# Intermediate_LCL_Top_20230320.net
KiCad netlist of a schematic drawn in Altium Designer
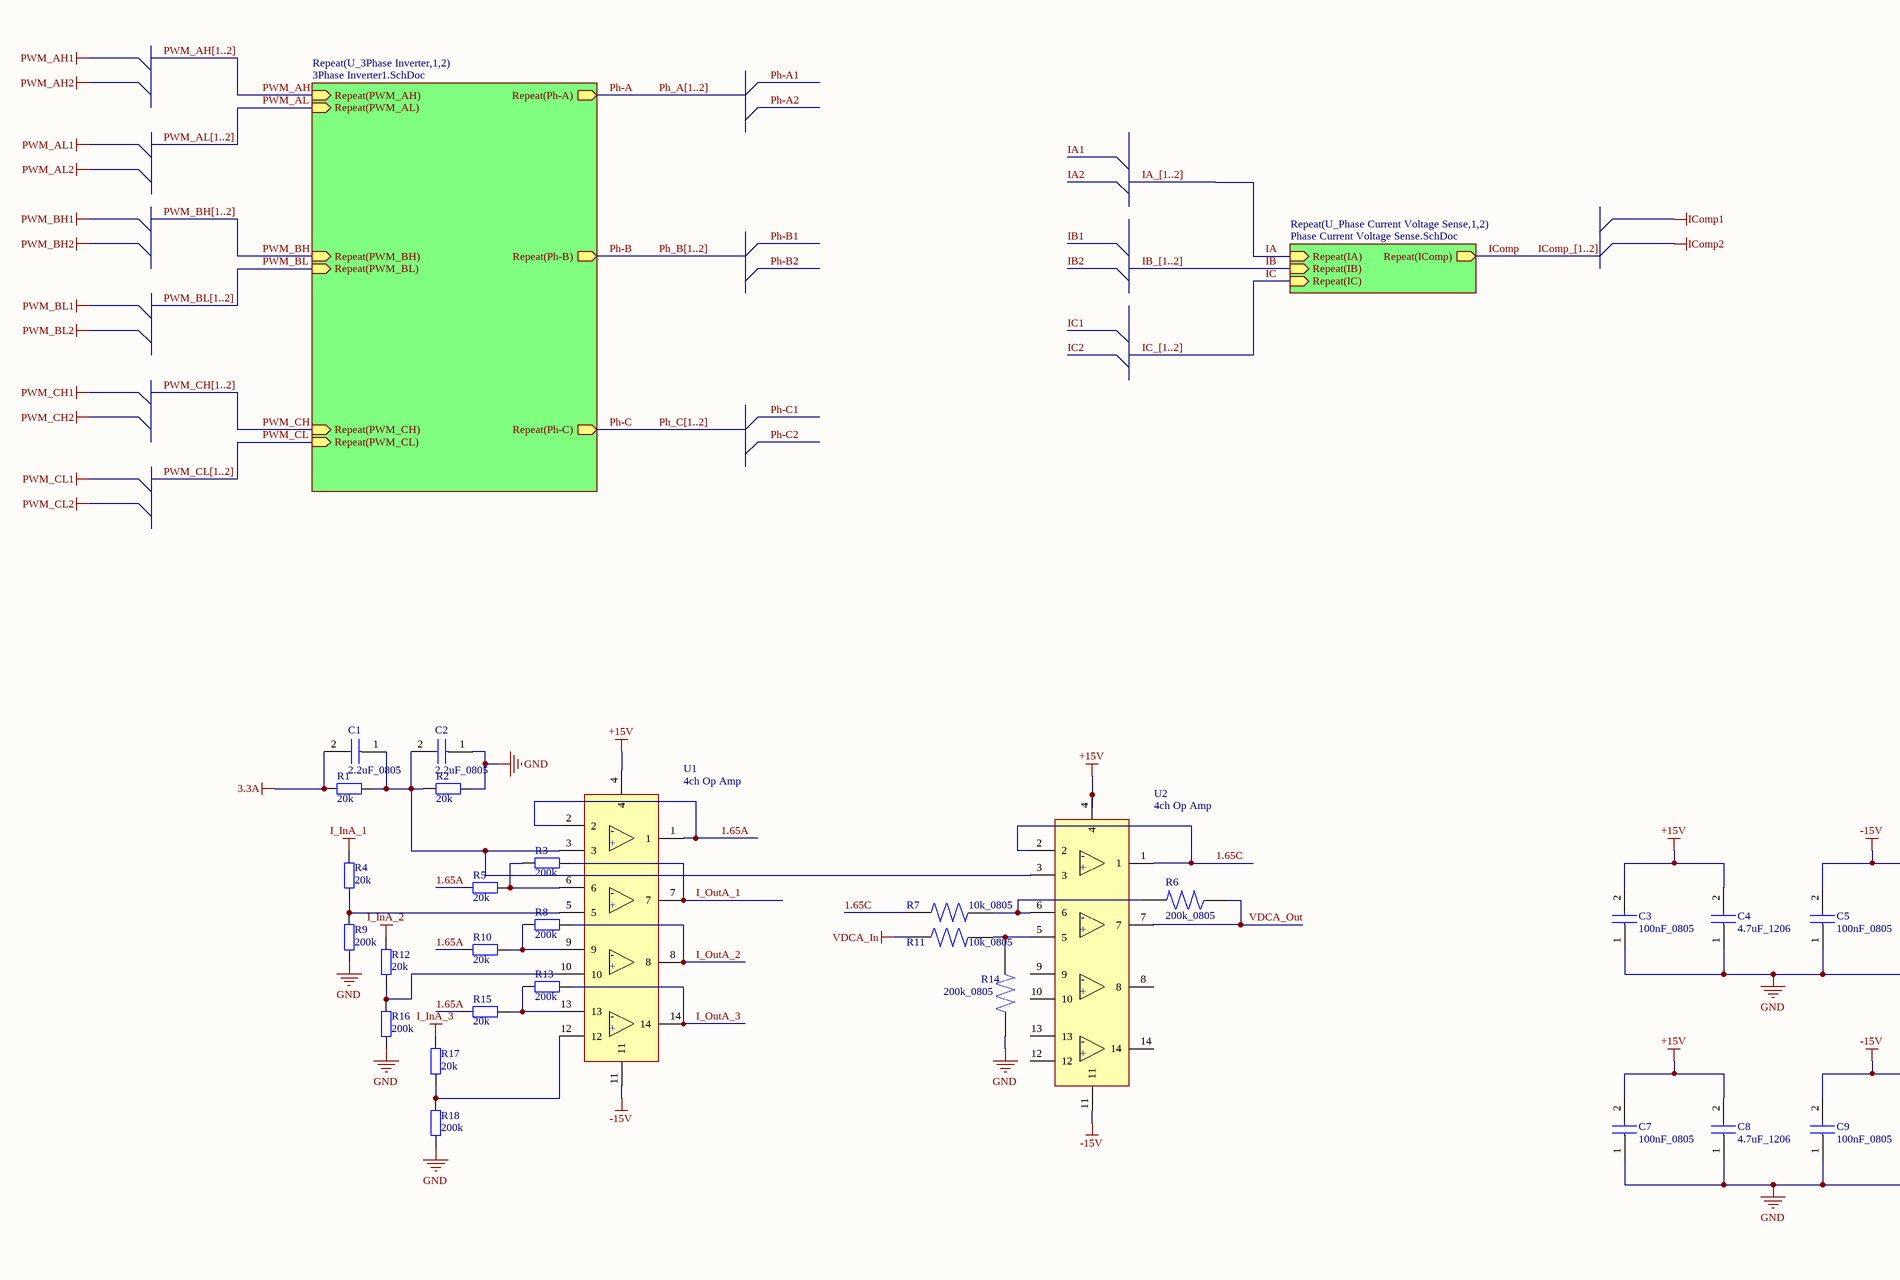
[diagram p0: Intermediate_LCL_Top_20230320.SchDoc, top left]
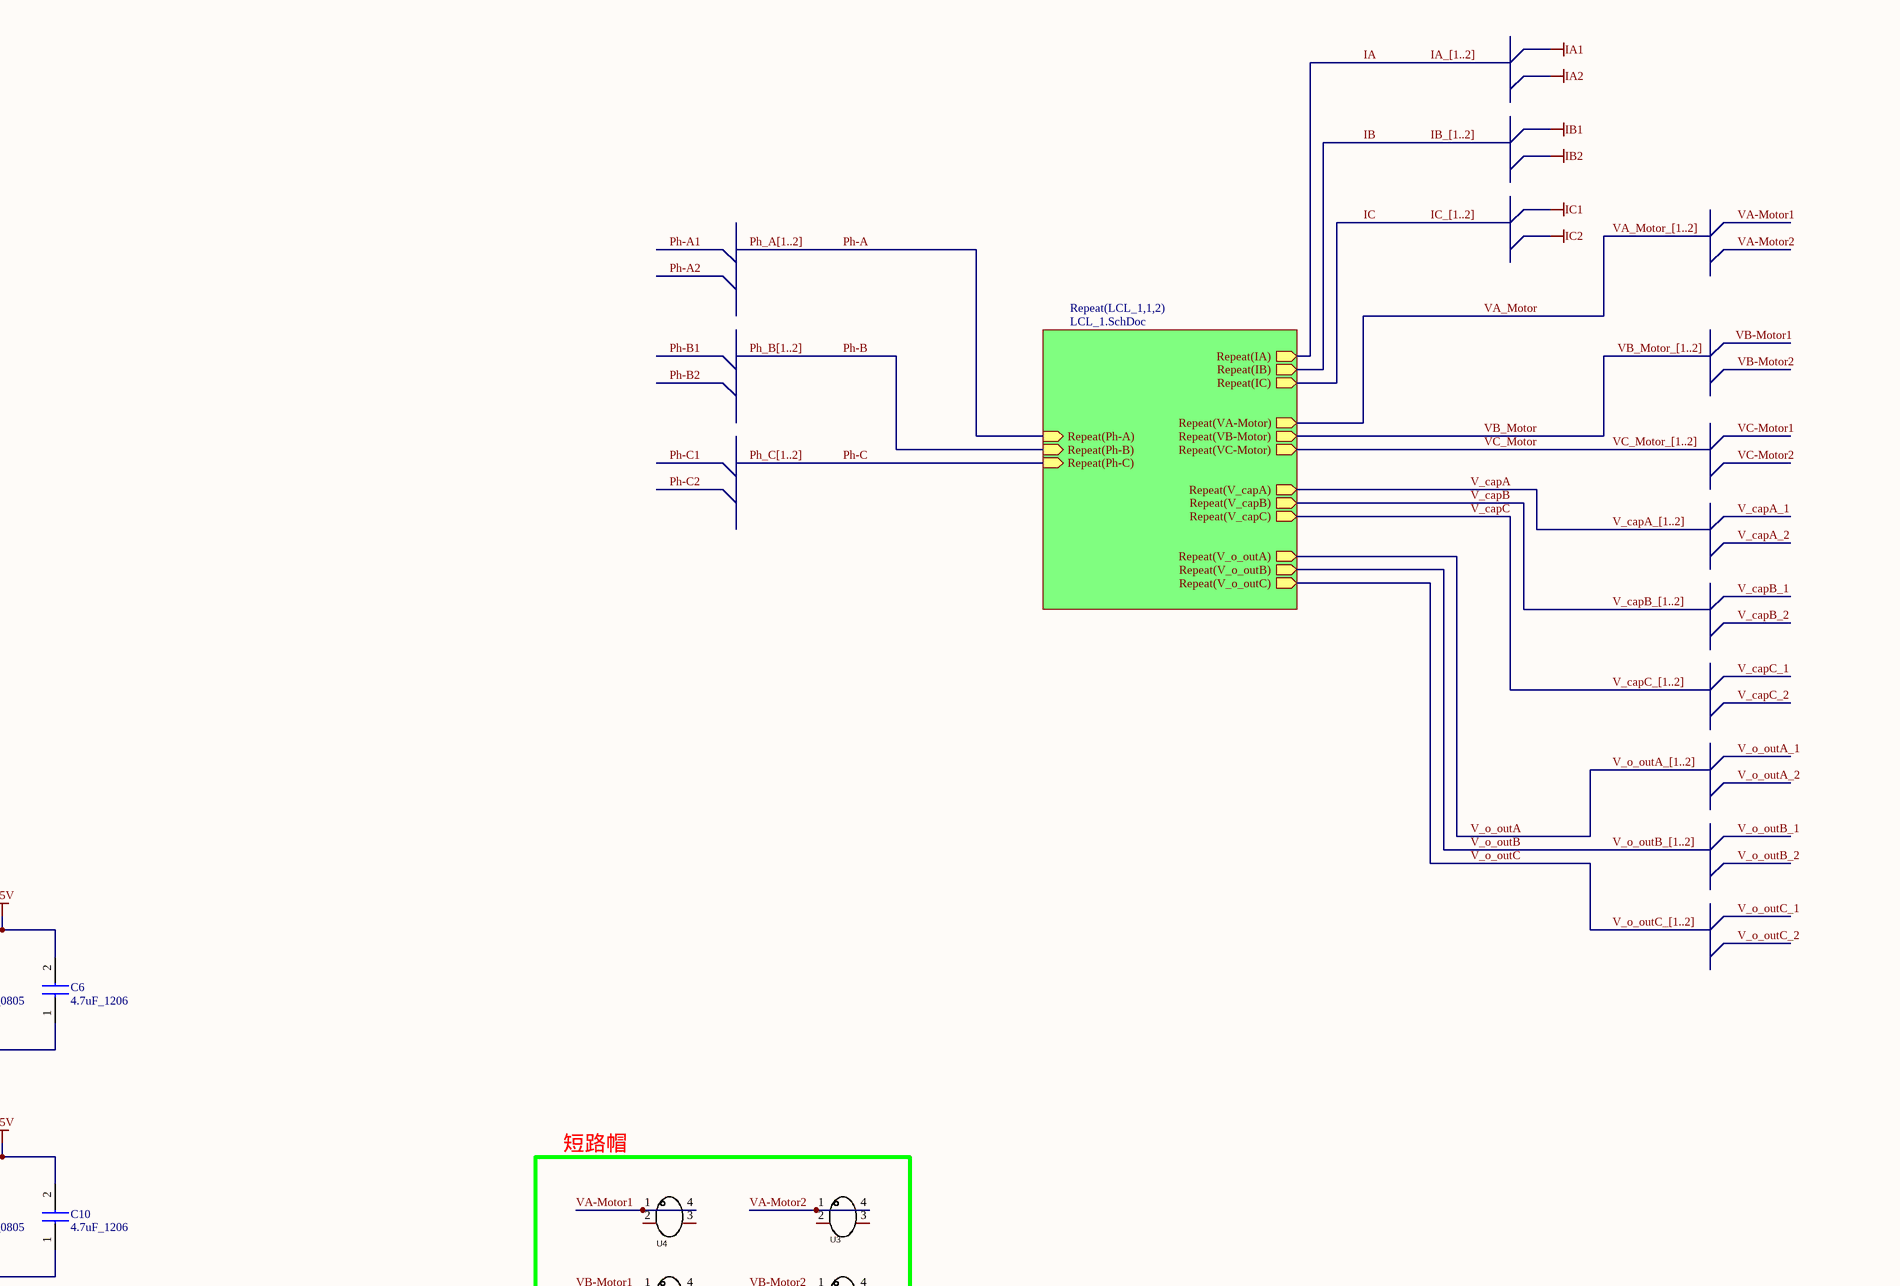
[diagram p1: Intermediate_LCL_Top_20230320.SchDoc, top right]
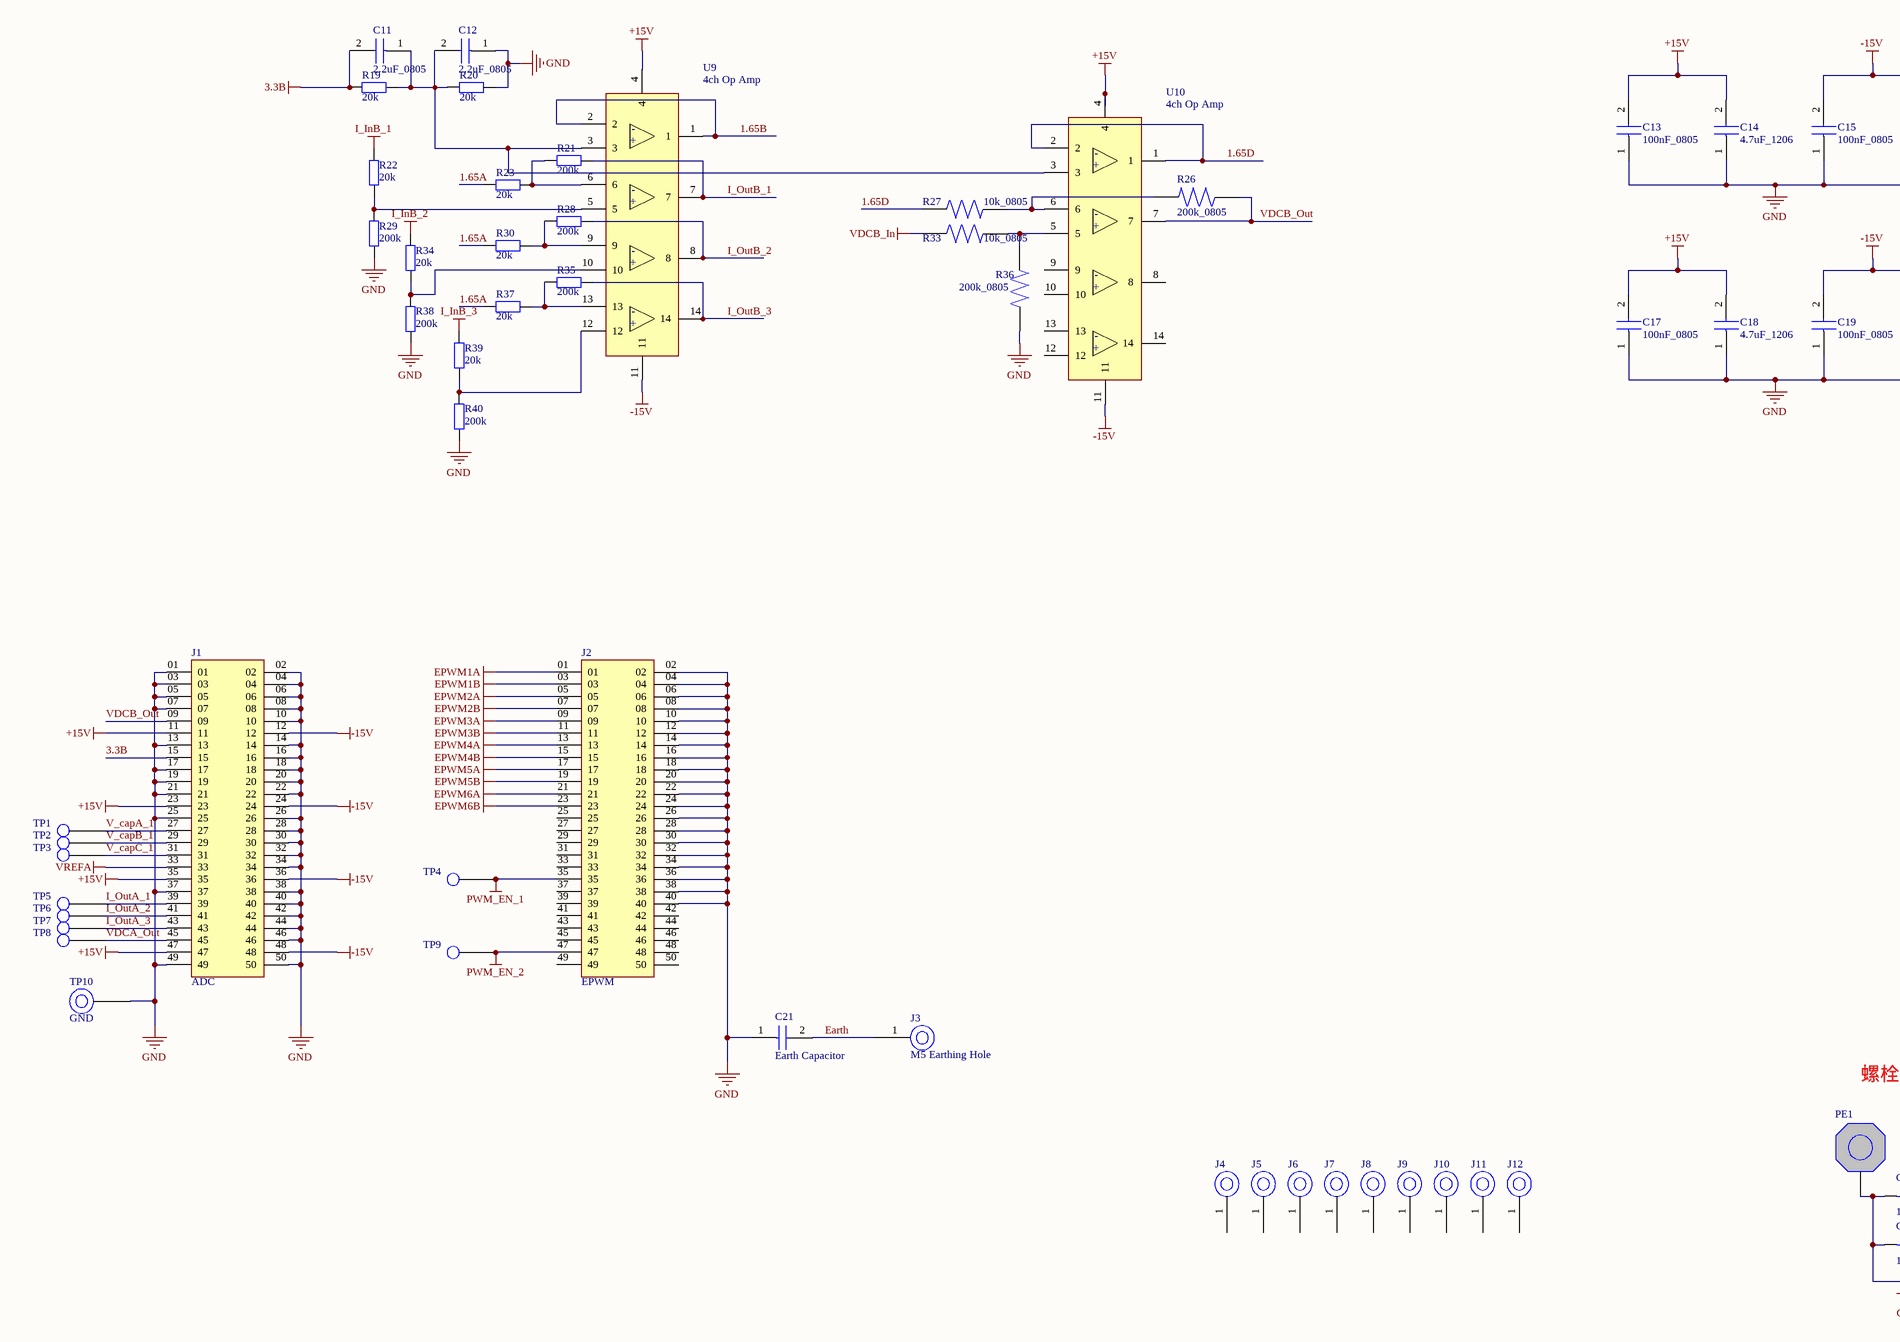
[diagram p2: Intermediate_LCL_Top_20230320.SchDoc, bottom left]
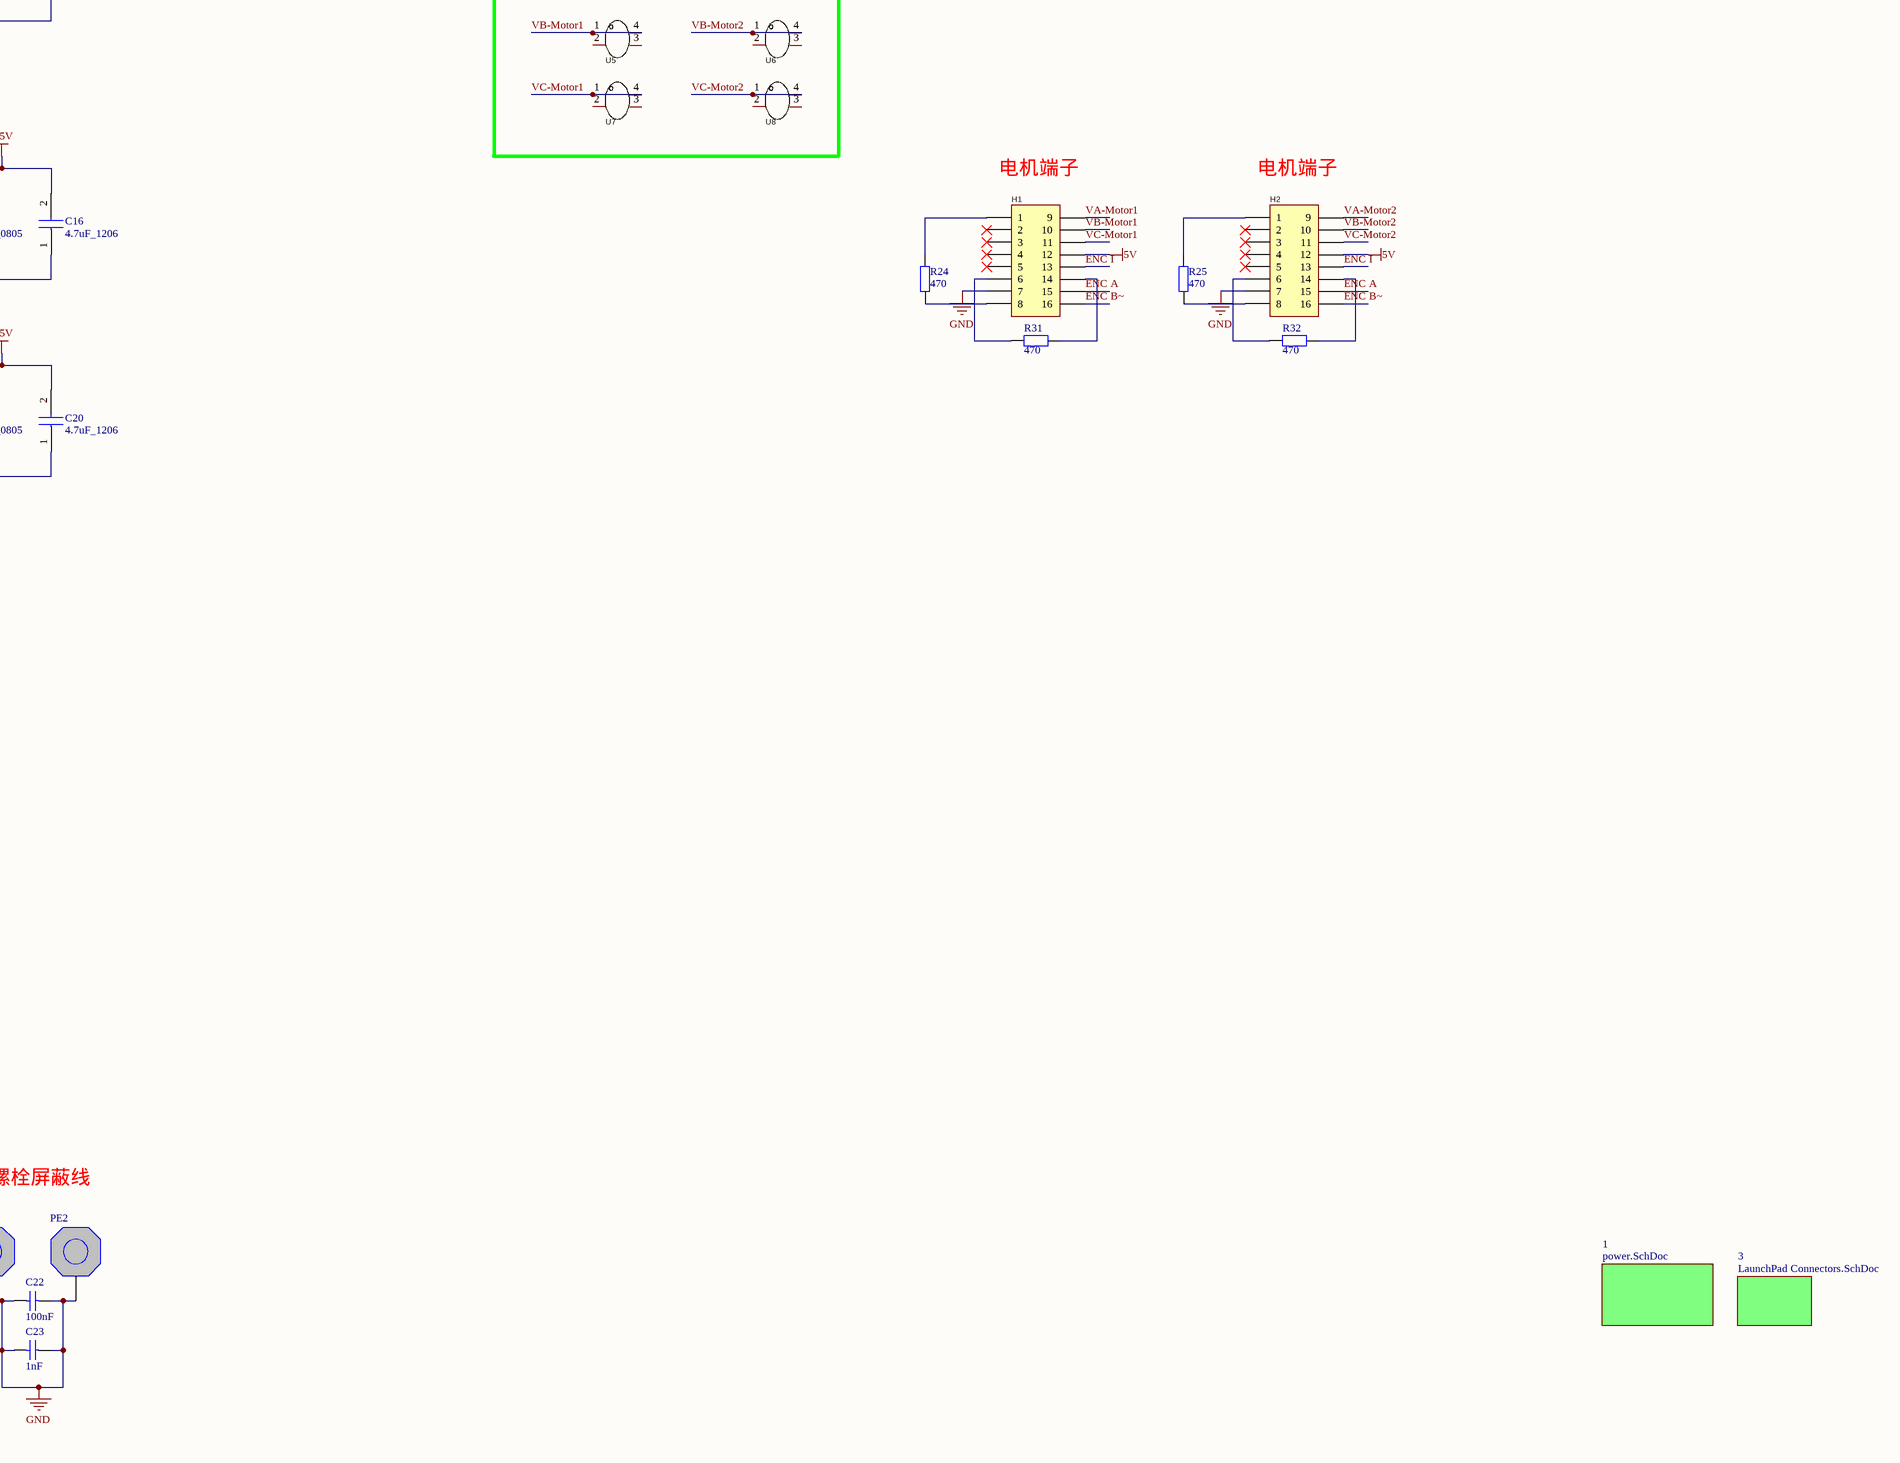
[diagram p3: Intermediate_LCL_Top_20230320.SchDoc, bottom right]

(export (version "E")
  (design (tool "Eeschema 10.0.6"))
  (components
    (comp (ref "C1")
      (value "2.2uF_0805")
      (footprint "CAPC1608X06N")
      (description "SMD Multilayer Ceramic Capacitor, 2.2 µF, 50 V, 0805 [2012 Metric], ± 10%, X5R, C")
      (libsource (lib "FYP_Components") (part "C2012X5R1H225K125AB"))
    )
    (comp (ref "C2")
      (value "2.2uF_0805")
      (footprint "CAPC1608X06N")
      (description "SMD Multilayer Ceramic Capacitor, 2.2 µF, 50 V, 0805 [2012 Metric], ± 10%, X5R, C")
      (libsource (lib "FYP_Components") (part "C2012X5R1H225K125AB"))
    )
    (comp (ref "C3")
      (value "100nF_0805")
      (footprint "CAPC1608X06N")
      (description "SMD Multilayer Ceramic Capacitor, 0.1 µF, 50 V, 0805 [2012 Metric], ± 5%, X7R, C Series KEMET")
      (libsource (lib "FYP_Components") (part "C0805C104J5RACTU"))
    )
    (comp (ref "C4")
      (value "4.7uF_1206")
      (footprint "CAPC1608X06N")
      (description "SMD Multilayer Ceramic Capacitor, 4.7 µF, 50 V, 1206 [3216 Metric], ± 10%, X7R, C")
      (fields (field (name "MP") "C1206C120J5GACTU"))
      (libsource (lib "FYP_Components") (part "C3216X7R1H475K160AC"))
    )
    (comp (ref "C5")
      (value "100nF_0805")
      (footprint "CAPC1608X06N")
      (description "SMD Multilayer Ceramic Capacitor, 0.1 µF, 50 V, 0805 [2012 Metric], ± 5%, X7R, C Series KEMET")
      (libsource (lib "FYP_Components") (part "C0805C104J5RACTU"))
    )
    (comp (ref "C6")
      (value "4.7uF_1206")
      (footprint "CAPC1608X06N")
      (description "SMD Multilayer Ceramic Capacitor, 4.7 µF, 50 V, 1206 [3216 Metric], ± 10%, X7R, C")
      (fields (field (name "MP") "C1206C120J5GACTU"))
      (libsource (lib "FYP_Components") (part "C3216X7R1H475K160AC"))
    )
    (comp (ref "C7")
      (value "100nF_0805")
      (footprint "CAPC1608X06N")
      (description "SMD Multilayer Ceramic Capacitor, 0.1 µF, 50 V, 0805 [2012 Metric], ± 5%, X7R, C Series KEMET")
      (libsource (lib "FYP_Components") (part "C0805C104J5RACTU"))
    )
    (comp (ref "C8")
      (value "4.7uF_1206")
      (footprint "CAPC1608X06N")
      (description "SMD Multilayer Ceramic Capacitor, 4.7 µF, 50 V, 1206 [3216 Metric], ± 10%, X7R, C")
      (fields (field (name "MP") "C1206C120J5GACTU"))
      (libsource (lib "FYP_Components") (part "C3216X7R1H475K160AC"))
    )
    (comp (ref "C9")
      (value "100nF_0805")
      (footprint "CAPC1608X06N")
      (description "SMD Multilayer Ceramic Capacitor, 0.1 µF, 50 V, 0805 [2012 Metric], ± 5%, X7R, C Series KEMET")
      (libsource (lib "FYP_Components") (part "C0805C104J5RACTU"))
    )
    (comp (ref "C10")
      (value "4.7uF_1206")
      (footprint "CAPC1608X06N")
      (description "SMD Multilayer Ceramic Capacitor, 4.7 µF, 50 V, 1206 [3216 Metric], ± 10%, X7R, C")
      (fields (field (name "MP") "C1206C120J5GACTU"))
      (libsource (lib "FYP_Components") (part "C3216X7R1H475K160AC"))
    )
    (comp (ref "C11")
      (value "2.2uF_0805")
      (footprint "CAPC1608X06N")
      (description "SMD Multilayer Ceramic Capacitor, 2.2 µF, 50 V, 0805 [2012 Metric], ± 10%, X5R, C")
      (libsource (lib "FYP_Components") (part "C2012X5R1H225K125AB"))
    )
    (comp (ref "C12")
      (value "2.2uF_0805")
      (footprint "CAPC1608X06N")
      (description "SMD Multilayer Ceramic Capacitor, 2.2 µF, 50 V, 0805 [2012 Metric], ± 10%, X5R, C")
      (libsource (lib "FYP_Components") (part "C2012X5R1H225K125AB"))
    )
    (comp (ref "C13")
      (value "100nF_0805")
      (footprint "CAPC1608X06N")
      (description "SMD Multilayer Ceramic Capacitor, 0.1 µF, 50 V, 0805 [2012 Metric], ± 5%, X7R, C Series KEMET")
      (libsource (lib "FYP_Components") (part "C0805C104J5RACTU"))
    )
    (comp (ref "C14")
      (value "4.7uF_1206")
      (footprint "CAPC1608X06N")
      (description "SMD Multilayer Ceramic Capacitor, 4.7 µF, 50 V, 1206 [3216 Metric], ± 10%, X7R, C")
      (fields (field (name "MP") "C1206C120J5GACTU"))
      (libsource (lib "FYP_Components") (part "C3216X7R1H475K160AC"))
    )
    (comp (ref "C15")
      (value "100nF_0805")
      (footprint "CAPC1608X06N")
      (description "SMD Multilayer Ceramic Capacitor, 0.1 µF, 50 V, 0805 [2012 Metric], ± 5%, X7R, C Series KEMET")
      (libsource (lib "FYP_Components") (part "C0805C104J5RACTU"))
    )
    (comp (ref "C16")
      (value "4.7uF_1206")
      (footprint "CAPC1608X06N")
      (description "SMD Multilayer Ceramic Capacitor, 4.7 µF, 50 V, 1206 [3216 Metric], ± 10%, X7R, C")
      (fields (field (name "MP") "C1206C120J5GACTU"))
      (libsource (lib "FYP_Components") (part "C3216X7R1H475K160AC"))
    )
    (comp (ref "C17")
      (value "100nF_0805")
      (footprint "CAPC1608X06N")
      (description "SMD Multilayer Ceramic Capacitor, 0.1 µF, 50 V, 0805 [2012 Metric], ± 5%, X7R, C Series KEMET")
      (libsource (lib "FYP_Components") (part "C0805C104J5RACTU"))
    )
    (comp (ref "C18")
      (value "4.7uF_1206")
      (footprint "CAPC1608X06N")
      (description "SMD Multilayer Ceramic Capacitor, 4.7 µF, 50 V, 1206 [3216 Metric], ± 10%, X7R, C")
      (fields (field (name "MP") "C1206C120J5GACTU"))
      (libsource (lib "FYP_Components") (part "C3216X7R1H475K160AC"))
    )
    (comp (ref "C19")
      (value "100nF_0805")
      (footprint "CAPC1608X06N")
      (description "SMD Multilayer Ceramic Capacitor, 0.1 µF, 50 V, 0805 [2012 Metric], ± 5%, X7R, C Series KEMET")
      (libsource (lib "FYP_Components") (part "C0805C104J5RACTU"))
    )
    (comp (ref "C20")
      (value "4.7uF_1206")
      (footprint "CAPC1608X06N")
      (description "SMD Multilayer Ceramic Capacitor, 4.7 µF, 50 V, 1206 [3216 Metric], ± 10%, X7R, C")
      (fields (field (name "MP") "C1206C120J5GACTU"))
      (libsource (lib "FYP_Components") (part "C3216X7R1H475K160AC"))
    )
    (comp (ref "C21")
      (value "Earth Capacitor")
      (footprint "RAD-0.3")
      (description "Y Earth Capacitor")
      (fields (field (name "MP") "C1206C120J5GACTU"))
      (libsource (lib "FYP_Components") (part "102_Y"))
    )
    (comp (ref "C22")
      (value "100nF")
      (footprint "CAPC1608X06N")
      (description "Capacitor")
      (fields (field (name "PUBLISHER") "Altium Limited"))
      (libsource (lib "Simscale") (part "Cap"))
    )
    (comp (ref "C23")
      (value "1nF")
      (footprint "CAPC1608X06N")
      (description "Capacitor")
      (fields (field (name "PUBLISHER") "Altium Limited"))
      (libsource (lib "Simscale") (part "Cap"))
    )
    (comp (ref "H1")
      (value "HC-5557-2*8AW")
      (footprint "CONN-TH_16P-P4.20_5557-2X8AW")
      (fields (field (name "MANUFACTURER") "HCTL(华灿天禄)"))
      (libsource (lib "HC-5557-2_8AW1_HC-5557-2_8AW.schdoc") (part "HC-5557-2*8AW"))
    )
    (comp (ref "H2")
      (value "HC-5557-2*8AW")
      (footprint "CONN-TH_16P-P4.20_5557-2X8AW")
      (fields (field (name "MANUFACTURER") "HCTL(华灿天禄)"))
      (libsource (lib "HC-5557-2_8AW1_HC-5557-2_8AW.schdoc") (part "HC-5557-2*8AW"))
    )
    (comp (ref "J1")
      (value "ADC")
      (footprint "SHF-125-01-L-D-RA")
      (description "50-Pin Simplus Connector")
      (fields (field (name "MP") "SHF-125-01-L-D-RA") (field (name "MF") "Samtec"))
      (libsource (lib "FYP_Components") (part "SHF-125-01-L-D-RA"))
    )
    (comp (ref "J2")
      (value "EPWM")
      (footprint "SHF-125-01-L-D-RA")
      (description "50-Pin Simplus Connector")
      (fields (field (name "MP") "SHF-125-01-L-D-RA") (field (name "MF") "Samtec"))
      (libsource (lib "FYP_Components") (part "SHF-125-01-L-D-RA"))
    )
    (comp (ref "J3")
      (value "M5 Earthing Hole")
      (footprint "M5 Earthing Hole")
      (libsource (lib "FYP_Components") (part "M5 Earthing Hole"))
    )
    (comp (ref "J4")
      (value "M5 Mounting Hole")
      (footprint "M5 Mounting Hole")
      (libsource (lib "FYP_Components") (part "M5 Mounting Hole"))
    )
    (comp (ref "J5")
      (value "M5 Mounting Hole")
      (footprint "M5 Mounting Hole")
      (libsource (lib "FYP_Components") (part "M5 Mounting Hole"))
    )
    (comp (ref "J6")
      (value "M5 Mounting Hole")
      (footprint "M5 Mounting Hole")
      (libsource (lib "FYP_Components") (part "M5 Mounting Hole"))
    )
    (comp (ref "J7")
      (value "M5 Mounting Hole")
      (footprint "M5 Mounting Hole")
      (libsource (lib "FYP_Components") (part "M5 Mounting Hole"))
    )
    (comp (ref "J8")
      (value "M5 Mounting Hole")
      (footprint "M5 Mounting Hole")
      (libsource (lib "FYP_Components") (part "M5 Mounting Hole"))
    )
    (comp (ref "J9")
      (value "M5 Mounting Hole")
      (footprint "M5 Mounting Hole")
      (libsource (lib "FYP_Components") (part "M5 Mounting Hole"))
    )
    (comp (ref "J10")
      (value "M5 Mounting Hole")
      (footprint "M5 Mounting Hole")
      (libsource (lib "FYP_Components") (part "M5 Mounting Hole"))
    )
    (comp (ref "J11")
      (value "M5 Mounting Hole")
      (footprint "M5 Mounting Hole")
      (libsource (lib "FYP_Components") (part "M5 Mounting Hole"))
    )
    (comp (ref "J12")
      (value "M5 Mounting Hole")
      (footprint "M5 Mounting Hole")
      (libsource (lib "FYP_Components") (part "M5 Mounting Hole"))
    )
    (comp (ref "PE1") (value "PE") (footprint "PE1") (libsource (lib "Soardra") (part "PE")))
    (comp (ref "PE2") (value "PE") (footprint "PE1") (libsource (lib "Soardra") (part "PE")))
    (comp (ref "R1")
      (value "20k")
      (footprint "RESC1608X05N")
      (description "贴片电阻")
      (libsource (lib "") (part "0603 100KΩ (1003) 1%_4_1"))
    )
    (comp (ref "R2")
      (value "20k")
      (footprint "RESC1608X05N")
      (description "贴片电阻")
      (libsource (lib "") (part "0603 100KΩ (1003) 1%_4_1"))
    )
    (comp (ref "R3")
      (value "200k")
      (footprint "RESC1608X05N")
      (description "贴片电阻")
      (libsource (lib "") (part "0603 100KΩ (1003) 1%_4_1"))
    )
    (comp (ref "R4")
      (value "20k")
      (footprint "RESC1608X05N")
      (description "贴片电阻")
      (libsource (lib "Simscale") (part "0603 100KΩ (1003) 1%_4"))
    )
    (comp (ref "R5")
      (value "20k")
      (footprint "RESC1608X05N")
      (description "贴片电阻")
      (libsource (lib "") (part "0603 100KΩ (1003) 1%_4_1"))
    )
    (comp (ref "R6")
      (value "200k_0805")
      (footprint "RESC1608X05N")
      (description "SMD Chip Resistor, 200 kohm, ± 1%, 125 mW, 0805 [2012 Metric], Thick Film, General Purpose")
      (fields (field (name "MF") "Bourns") (field (name "MP") "CRE2512-FZ-R007E-3"))
      (libsource (lib "FYP_Components") (part "CRCW0805200KFKEA"))
    )
    (comp (ref "R7")
      (value "10k_0805")
      (footprint "RESC1608X05N")
      (description "SMD Chip Resistor, 10 kohm, ± 1%, 125 mW, 0805 [2012 Metric], Thick Film, General Purpose")
      (fields (field (name "MF") "Bourns") (field (name "MP") "CRE2512-FZ-R007E-3"))
      (libsource (lib "FYP_Components") (part "CRCW080510K0FKEA"))
    )
    (comp (ref "R8")
      (value "200k")
      (footprint "RESC1608X05N")
      (description "贴片电阻")
      (libsource (lib "") (part "0603 100KΩ (1003) 1%_4_1"))
    )
    (comp (ref "R9")
      (value "200k")
      (footprint "RESC1608X05N")
      (description "贴片电阻")
      (libsource (lib "Simscale") (part "0603 100KΩ (1003) 1%_4"))
    )
    (comp (ref "R10")
      (value "20k")
      (footprint "RESC1608X05N")
      (description "贴片电阻")
      (libsource (lib "") (part "0603 100KΩ (1003) 1%_4_1"))
    )
    (comp (ref "R11")
      (value "10k_0805")
      (footprint "RESC1608X05N")
      (description "SMD Chip Resistor, 10 kohm, ± 1%, 125 mW, 0805 [2012 Metric], Thick Film, General Purpose")
      (fields (field (name "MF") "Bourns") (field (name "MP") "CRE2512-FZ-R007E-3"))
      (libsource (lib "FYP_Components") (part "CRCW080510K0FKEA"))
    )
    (comp (ref "R12")
      (value "20k")
      (footprint "RESC1608X05N")
      (description "贴片电阻")
      (libsource (lib "Simscale") (part "0603 100KΩ (1003) 1%_4"))
    )
    (comp (ref "R13")
      (value "200k")
      (footprint "RESC1608X05N")
      (description "贴片电阻")
      (libsource (lib "") (part "0603 100KΩ (1003) 1%_4_1"))
    )
    (comp (ref "R14")
      (value "200k_0805")
      (footprint "RESC1608X05N")
      (description "SMD Chip Resistor, 200 kohm, ± 1%, 125 mW, 0805 [2012 Metric], Thick Film, General Purpose")
      (fields (field (name "MF") "Bourns") (field (name "MP") "CRE2512-FZ-R007E-3"))
      (libsource (lib "FYP_Components") (part "CRCW0805200KFKEA"))
    )
    (comp (ref "R15")
      (value "20k")
      (footprint "RESC1608X05N")
      (description "贴片电阻")
      (libsource (lib "") (part "0603 100KΩ (1003) 1%_4_1"))
    )
    (comp (ref "R16")
      (value "200k")
      (footprint "RESC1608X05N")
      (description "贴片电阻")
      (libsource (lib "Simscale") (part "0603 100KΩ (1003) 1%_4"))
    )
    (comp (ref "R17")
      (value "20k")
      (footprint "RESC1608X05N")
      (description "贴片电阻")
      (libsource (lib "Simscale") (part "0603 100KΩ (1003) 1%_4"))
    )
    (comp (ref "R18")
      (value "200k")
      (footprint "RESC1608X05N")
      (description "贴片电阻")
      (libsource (lib "Simscale") (part "0603 100KΩ (1003) 1%_4"))
    )
    (comp (ref "R19")
      (value "20k")
      (footprint "RESC1608X05N")
      (description "贴片电阻")
      (libsource (lib "") (part "0603 100KΩ (1003) 1%_4_1"))
    )
    (comp (ref "R20")
      (value "20k")
      (footprint "RESC1608X05N")
      (description "贴片电阻")
      (libsource (lib "") (part "0603 100KΩ (1003) 1%_4_1"))
    )
    (comp (ref "R21")
      (value "200k")
      (footprint "RESC1608X05N")
      (description "贴片电阻")
      (libsource (lib "") (part "0603 100KΩ (1003) 1%_4_1"))
    )
    (comp (ref "R22")
      (value "20k")
      (footprint "RESC1608X05N")
      (description "贴片电阻")
      (libsource (lib "Simscale") (part "0603 100KΩ (1003) 1%_4"))
    )
    (comp (ref "R23")
      (value "20k")
      (footprint "RESC1608X05N")
      (description "贴片电阻")
      (libsource (lib "") (part "0603 100KΩ (1003) 1%_4_1"))
    )
    (comp (ref "R24")
      (value "470")
      (footprint "RESC1608X05N")
      (description "贴片电阻")
      (libsource (lib "Simscale") (part "0603 100KΩ (1003) 1%_4"))
    )
    (comp (ref "R25")
      (value "470")
      (footprint "RESC1608X05N")
      (description "贴片电阻")
      (libsource (lib "Simscale") (part "0603 100KΩ (1003) 1%_4"))
    )
    (comp (ref "R26")
      (value "200k_0805")
      (footprint "RESC1608X05N")
      (description "SMD Chip Resistor, 200 kohm, ± 1%, 125 mW, 0805 [2012 Metric], Thick Film, General Purpose")
      (fields (field (name "MF") "Bourns") (field (name "MP") "CRE2512-FZ-R007E-3"))
      (libsource (lib "FYP_Components") (part "CRCW0805200KFKEA"))
    )
    (comp (ref "R27")
      (value "10k_0805")
      (footprint "RESC1608X05N")
      (description "SMD Chip Resistor, 10 kohm, ± 1%, 125 mW, 0805 [2012 Metric], Thick Film, General Purpose")
      (fields (field (name "MF") "Bourns") (field (name "MP") "CRE2512-FZ-R007E-3"))
      (libsource (lib "FYP_Components") (part "CRCW080510K0FKEA"))
    )
    (comp (ref "R28")
      (value "200k")
      (footprint "RESC1608X05N")
      (description "贴片电阻")
      (libsource (lib "") (part "0603 100KΩ (1003) 1%_4_1"))
    )
    (comp (ref "R29")
      (value "200k")
      (footprint "RESC1608X05N")
      (description "贴片电阻")
      (libsource (lib "Simscale") (part "0603 100KΩ (1003) 1%_4"))
    )
    (comp (ref "R30")
      (value "20k")
      (footprint "RESC1608X05N")
      (description "贴片电阻")
      (libsource (lib "") (part "0603 100KΩ (1003) 1%_4_1"))
    )
    (comp (ref "R31")
      (value "470")
      (footprint "RESC1608X05N")
      (description "贴片电阻")
      (libsource (lib "") (part "0603 100KΩ (1003) 1%_4_1"))
    )
    (comp (ref "R32")
      (value "470")
      (footprint "RESC1608X05N")
      (description "贴片电阻")
      (libsource (lib "") (part "0603 100KΩ (1003) 1%_4_1"))
    )
    (comp (ref "R33")
      (value "10k_0805")
      (footprint "RESC1608X05N")
      (description "SMD Chip Resistor, 10 kohm, ± 1%, 125 mW, 0805 [2012 Metric], Thick Film, General Purpose")
      (fields (field (name "MF") "Bourns") (field (name "MP") "CRE2512-FZ-R007E-3"))
      (libsource (lib "FYP_Components") (part "CRCW080510K0FKEA"))
    )
    (comp (ref "R34")
      (value "20k")
      (footprint "RESC1608X05N")
      (description "贴片电阻")
      (libsource (lib "Simscale") (part "0603 100KΩ (1003) 1%_4"))
    )
    (comp (ref "R35")
      (value "200k")
      (footprint "RESC1608X05N")
      (description "贴片电阻")
      (libsource (lib "") (part "0603 100KΩ (1003) 1%_4_1"))
    )
    (comp (ref "R36")
      (value "200k_0805")
      (footprint "RESC1608X05N")
      (description "SMD Chip Resistor, 200 kohm, ± 1%, 125 mW, 0805 [2012 Metric], Thick Film, General Purpose")
      (fields (field (name "MF") "Bourns") (field (name "MP") "CRE2512-FZ-R007E-3"))
      (libsource (lib "FYP_Components") (part "CRCW0805200KFKEA"))
    )
    (comp (ref "R37")
      (value "20k")
      (footprint "RESC1608X05N")
      (description "贴片电阻")
      (libsource (lib "") (part "0603 100KΩ (1003) 1%_4_1"))
    )
    (comp (ref "R38")
      (value "200k")
      (footprint "RESC1608X05N")
      (description "贴片电阻")
      (libsource (lib "Simscale") (part "0603 100KΩ (1003) 1%_4"))
    )
    (comp (ref "R39")
      (value "20k")
      (footprint "RESC1608X05N")
      (description "贴片电阻")
      (libsource (lib "Simscale") (part "0603 100KΩ (1003) 1%_4"))
    )
    (comp (ref "R40")
      (value "200k")
      (footprint "RESC1608X05N")
      (description "贴片电阻")
      (libsource (lib "Simscale") (part "0603 100KΩ (1003) 1%_4"))
    )
    (comp (ref "TP1")
      (value "VC_1A")
      (footprint "PCB 1.32mm TestPoint")
      (description "20-313143 PCB Test Point, White, Through Hole Mount, 1.32 mm, Phosphor Bronze, Tin Plated Contacts")
      (libsource (lib "FYP_Components") (part "PCBTestpoint"))
    )
    (comp (ref "TP2")
      (value "VC_1B")
      (footprint "PCB 1.32mm TestPoint")
      (description "20-313143 PCB Test Point, White, Through Hole Mount, 1.32 mm, Phosphor Bronze, Tin Plated Contacts")
      (libsource (lib "FYP_Components") (part "PCBTestpoint"))
    )
    (comp (ref "TP3")
      (value "VC_1C")
      (footprint "PCB 1.32mm TestPoint")
      (description "20-313143 PCB Test Point, White, Through Hole Mount, 1.32 mm, Phosphor Bronze, Tin Plated Contacts")
      (libsource (lib "FYP_Components") (part "PCBTestpoint"))
    )
    (comp (ref "TP4")
      (value "PWMEN1")
      (footprint "PCB 1.32mm TestPoint")
      (description "20-313143 PCB Test Point, White, Through Hole Mount, 1.32 mm, Phosphor Bronze, Tin Plated Contacts")
      (libsource (lib "FYP_Components") (part "PCBTestpoint"))
    )
    (comp (ref "TP5")
      (value "I1")
      (footprint "PCB 1.32mm TestPoint")
      (description "20-313143 PCB Test Point, White, Through Hole Mount, 1.32 mm, Phosphor Bronze, Tin Plated Contacts")
      (libsource (lib "FYP_Components") (part "PCBTestpoint"))
    )
    (comp (ref "TP6")
      (value "I2")
      (footprint "PCB 1.32mm TestPoint")
      (description "20-313143 PCB Test Point, White, Through Hole Mount, 1.32 mm, Phosphor Bronze, Tin Plated Contacts")
      (libsource (lib "FYP_Components") (part "PCBTestpoint"))
    )
    (comp (ref "TP7")
      (value "I3")
      (footprint "PCB 1.32mm TestPoint")
      (description "20-313143 PCB Test Point, White, Through Hole Mount, 1.32 mm, Phosphor Bronze, Tin Plated Contacts")
      (libsource (lib "FYP_Components") (part "PCBTestpoint"))
    )
    (comp (ref "TP8")
      (value "VDC")
      (footprint "PCB 1.32mm TestPoint")
      (description "20-313143 PCB Test Point, White, Through Hole Mount, 1.32 mm, Phosphor Bronze, Tin Plated Contacts")
      (libsource (lib "FYP_Components") (part "PCBTestpoint"))
    )
    (comp (ref "TP9")
      (value "PWMEN2")
      (footprint "PCB 1.32mm TestPoint")
      (description "20-313143 PCB Test Point, White, Through Hole Mount, 1.32 mm, Phosphor Bronze, Tin Plated Contacts")
      (libsource (lib "FYP_Components") (part "PCBTestpoint"))
    )
    (comp (ref "TP10")
      (value "GND")
      (footprint "1.9mm Hole")
      (description "H2182-01 PCB Test Point, PCB Mount, 1.9 mm, Brass, Tin Plated Contacts")
      (libsource (lib "FYP_Components") (part "GroundTestPoint"))
    )
    (comp (ref "U1")
      (value "4ch Op Amp")
      (footprint "SOIC-14")
      (description "Quad, 30-V, 3-MHz, high slew rate (13-V/µs), In to V+, JFET-input op amp")
      (libsource (lib "FYP_Components") (part "TL074D"))
    )
    (comp (ref "U2")
      (value "4ch Op Amp")
      (footprint "SOIC-14")
      (description "Quad, 30-V, 3-MHz, high slew rate (13-V/µs), In to V+, JFET-input op amp")
      (libsource (lib "FYP_Components") (part "TL074D"))
    )
    (comp (ref "U3")
      (value "TM54111092-1250")
      (footprint "CONN-TH_TM54111092-1250")
      (fields (field (name "MANUFACTURER") "XFCN(兴飞)"))
      (libsource (lib "TM54111092-12501_TM54111092-1250.schdoc") (part "TM54111092-1250"))
    )
    (comp (ref "U4")
      (value "TM54111092-1250")
      (footprint "CONN-TH_TM54111092-1250")
      (fields (field (name "MANUFACTURER") "XFCN(兴飞)"))
      (libsource (lib "TM54111092-12501_TM54111092-1250.schdoc") (part "TM54111092-1250"))
    )
    (comp (ref "U5")
      (value "TM54111092-1250")
      (footprint "CONN-TH_TM54111092-1250")
      (fields (field (name "MANUFACTURER") "XFCN(兴飞)"))
      (libsource (lib "TM54111092-12501_TM54111092-1250.schdoc") (part "TM54111092-1250"))
    )
    (comp (ref "U6")
      (value "TM54111092-1250")
      (footprint "CONN-TH_TM54111092-1250")
      (fields (field (name "MANUFACTURER") "XFCN(兴飞)"))
      (libsource (lib "TM54111092-12501_TM54111092-1250.schdoc") (part "TM54111092-1250"))
    )
    (comp (ref "U7")
      (value "TM54111092-1250")
      (footprint "CONN-TH_TM54111092-1250")
      (fields (field (name "MANUFACTURER") "XFCN(兴飞)"))
      (libsource (lib "TM54111092-12501_TM54111092-1250.schdoc") (part "TM54111092-1250"))
    )
    (comp (ref "U8")
      (value "TM54111092-1250")
      (footprint "CONN-TH_TM54111092-1250")
      (fields (field (name "MANUFACTURER") "XFCN(兴飞)"))
      (libsource (lib "TM54111092-12501_TM54111092-1250.schdoc") (part "TM54111092-1250"))
    )
    (comp (ref "U9")
      (value "4ch Op Amp")
      (footprint "SOIC-14")
      (description "Quad, 30-V, 3-MHz, high slew rate (13-V/µs), In to V+, JFET-input op amp")
      (libsource (lib "FYP_Components") (part "TL074D"))
    )
    (comp (ref "U10")
      (value "4ch Op Amp")
      (footprint "SOIC-14")
      (description "Quad, 30-V, 3-MHz, high slew rate (13-V/µs), In to V+, JFET-input op amp")
      (libsource (lib "FYP_Components") (part "TL074D"))
    )
  )
  (nets
    (net (code "21") (name "+15V") (class "Default")
      (node (ref "C13") (pin "2") (pinfunction "2_2") (pintype "passive"))
      (node (ref "C14") (pin "2") (pinfunction "2_2") (pintype "passive"))
      (node (ref "C17") (pin "2") (pinfunction "2_2") (pintype "passive"))
      (node (ref "C18") (pin "2") (pinfunction "2_2") (pintype "passive"))
      (node (ref "C3") (pin "2") (pinfunction "2_2") (pintype "passive"))
      (node (ref "C4") (pin "2") (pinfunction "2_2") (pintype "passive"))
      (node (ref "C7") (pin "2") (pinfunction "2_2") (pintype "passive"))
      (node (ref "C8") (pin "2") (pinfunction "2_2") (pintype "passive"))
      (node (ref "J1") (pin "11") (pinfunction "11_11") (pintype "passive"))
      (node (ref "J1") (pin "23") (pinfunction "23_23") (pintype "passive"))
      (node (ref "J1") (pin "35") (pinfunction "35_35") (pintype "passive"))
      (node (ref "J1") (pin "47") (pinfunction "47_47") (pintype "passive"))
      (node (ref "U1") (pin "4") (pinfunction "4_4") (pintype "passive"))
      (node (ref "U10") (pin "4") (pinfunction "4_4") (pintype "passive"))
      (node (ref "U2") (pin "4") (pinfunction "4_4") (pintype "passive"))
      (node (ref "U9") (pin "4") (pinfunction "4_4") (pintype "passive"))
    )
    (net (code "22") (name "-15V") (class "Default")
      (node (ref "C10") (pin "2") (pinfunction "2_2") (pintype "passive"))
      (node (ref "C15") (pin "2") (pinfunction "2_2") (pintype "passive"))
      (node (ref "C16") (pin "2") (pinfunction "2_2") (pintype "passive"))
      (node (ref "C19") (pin "2") (pinfunction "2_2") (pintype "passive"))
      (node (ref "C20") (pin "2") (pinfunction "2_2") (pintype "passive"))
      (node (ref "C5") (pin "2") (pinfunction "2_2") (pintype "passive"))
      (node (ref "C6") (pin "2") (pinfunction "2_2") (pintype "passive"))
      (node (ref "C9") (pin "2") (pinfunction "2_2") (pintype "passive"))
      (node (ref "J1") (pin "12") (pinfunction "12_12") (pintype "passive"))
      (node (ref "J1") (pin "24") (pinfunction "24_24") (pintype "passive"))
      (node (ref "J1") (pin "36") (pinfunction "36_36") (pintype "passive"))
      (node (ref "J1") (pin "48") (pinfunction "48_48") (pintype "passive"))
      (node (ref "U1") (pin "11") (pinfunction "11_11") (pintype "passive"))
      (node (ref "U10") (pin "11") (pinfunction "11_11") (pintype "passive"))
      (node (ref "U2") (pin "11") (pinfunction "11_11") (pintype "passive"))
      (node (ref "U9") (pin "11") (pinfunction "11_11") (pintype "passive"))
    )
    (net (code "23") (name "/1.65A") (class "Default")
      (node (ref "R10") (pin "2") (pinfunction "2_2") (pintype "passive"))
      (node (ref "R15") (pin "2") (pinfunction "2_2") (pintype "passive"))
      (node (ref "R23") (pin "2") (pinfunction "2_2") (pintype "passive"))
      (node (ref "R30") (pin "2") (pinfunction "2_2") (pintype "passive"))
      (node (ref "R37") (pin "2") (pinfunction "2_2") (pintype "passive"))
      (node (ref "R5") (pin "2") (pinfunction "2_2") (pintype "passive"))
      (node (ref "U1") (pin "1") (pinfunction "1_1") (pintype "passive"))
      (node (ref "U1") (pin "2") (pinfunction "2_2") (pintype "passive"))
    )
    (net (code "24") (name "/1.65B") (class "Default")
      (node (ref "U9") (pin "1") (pinfunction "1_1") (pintype "passive"))
      (node (ref "U9") (pin "2") (pinfunction "2_2") (pintype "passive"))
    )
    (net (code "25") (name "/1.65C") (class "Default")
      (node (ref "R7") (pin "1") (pinfunction "1_1") (pintype "passive"))
      (node (ref "U2") (pin "1") (pinfunction "1_1") (pintype "passive"))
      (node (ref "U2") (pin "2") (pinfunction "2_2") (pintype "passive"))
    )
    (net (code "26") (name "/1.65D") (class "Default")
      (node (ref "R27") (pin "1") (pinfunction "1_1") (pintype "passive"))
      (node (ref "U10") (pin "1") (pinfunction "1_1") (pintype "passive"))
      (node (ref "U10") (pin "2") (pinfunction "2_2") (pintype "passive"))
    )
    (net (code "27") (name "/ENC A") (class "Default")
      (node (ref "H1") (pin "14") (pinfunction "15_14") (pintype "passive"))
      (node (ref "H2") (pin "14") (pinfunction "15_14") (pintype "passive"))
    )
    (net (code "28") (name "/ENC B~") (class "Default")
      (node (ref "H1") (pin "16") (pinfunction "16_16") (pintype "passive"))
      (node (ref "H2") (pin "16") (pinfunction "16_16") (pintype "passive"))
    )
    (net (code "29") (name "/ENC I") (class "Default")
      (node (ref "H1") (pin "10") (pinfunction "13_10") (pintype "passive"))
      (node (ref "H2") (pin "10") (pinfunction "13_10") (pintype "passive"))
    )
    (net (code "30") (name "/Earth") (class "Default")
      (node (ref "C21") (pin "2") (pinfunction "2_2") (pintype "passive"))
      (node (ref "J3") (pin "1") (pinfunction "1_1") (pintype "passive"))
    )
    (net (code "39") (name "/I_OutA_1") (class "Default")
      (node (ref "J1") (pin "39") (pinfunction "39_39") (pintype "passive"))
      (node (ref "R3") (pin "1") (pinfunction "1_1") (pintype "passive"))
      (node (ref "TP5") (pin "1") (pinfunction "1_1") (pintype "passive"))
      (node (ref "U1") (pin "7") (pinfunction "7_7") (pintype "passive"))
    )
    (net (code "40") (name "/I_OutA_2") (class "Default")
      (node (ref "J1") (pin "41") (pinfunction "41_41") (pintype "passive"))
      (node (ref "R8") (pin "1") (pinfunction "1_1") (pintype "passive"))
      (node (ref "TP6") (pin "1") (pinfunction "1_1") (pintype "passive"))
      (node (ref "U1") (pin "8") (pinfunction "8_8") (pintype "passive"))
    )
    (net (code "41") (name "/I_OutA_3") (class "Default")
      (node (ref "J1") (pin "43") (pinfunction "43_43") (pintype "passive"))
      (node (ref "R13") (pin "1") (pinfunction "1_1") (pintype "passive"))
      (node (ref "TP7") (pin "1") (pinfunction "1_1") (pintype "passive"))
      (node (ref "U1") (pin "14") (pinfunction "14_14") (pintype "passive"))
    )
    (net (code "42") (name "/I_OutB_1") (class "Default")
      (node (ref "R21") (pin "1") (pinfunction "1_1") (pintype "passive"))
      (node (ref "U9") (pin "7") (pinfunction "7_7") (pintype "passive"))
    )
    (net (code "43") (name "/I_OutB_2") (class "Default")
      (node (ref "R28") (pin "1") (pinfunction "1_1") (pintype "passive"))
      (node (ref "U9") (pin "8") (pinfunction "8_8") (pintype "passive"))
    )
    (net (code "44") (name "/I_OutB_3") (class "Default")
      (node (ref "R35") (pin "1") (pinfunction "1_1") (pintype "passive"))
      (node (ref "U9") (pin "14") (pinfunction "14_14") (pintype "passive"))
    )
    (net (code "69") (name "/VA-Motor1") (class "Default")
      (node (ref "H1") (pin "2") (pinfunction "9_2") (pintype "passive"))
      (node (ref "U4") (pin "1") (pinfunction "1_1") (pintype "passive"))
      (node (ref "U4") (pin "4") (pinfunction "4_4") (pintype "passive"))
    )
    (net (code "70") (name "/VA-Motor2") (class "Default")
      (node (ref "H2") (pin "2") (pinfunction "9_2") (pintype "passive"))
      (node (ref "U3") (pin "1") (pinfunction "1_1") (pintype "passive"))
      (node (ref "U3") (pin "4") (pinfunction "4_4") (pintype "passive"))
    )
    (net (code "73") (name "/VB-Motor1") (class "Default")
      (node (ref "H1") (pin "4") (pinfunction "10_4") (pintype "passive"))
      (node (ref "U5") (pin "1") (pinfunction "1_1") (pintype "passive"))
      (node (ref "U5") (pin "4") (pinfunction "4_4") (pintype "passive"))
    )
    (net (code "74") (name "/VB-Motor2") (class "Default")
      (node (ref "H2") (pin "4") (pinfunction "10_4") (pintype "passive"))
      (node (ref "U6") (pin "1") (pinfunction "1_1") (pintype "passive"))
      (node (ref "U6") (pin "4") (pinfunction "4_4") (pintype "passive"))
    )
    (net (code "77") (name "/VC-Motor1") (class "Default")
      (node (ref "H1") (pin "6") (pinfunction "11_6") (pintype "passive"))
      (node (ref "U7") (pin "1") (pinfunction "1_1") (pintype "passive"))
      (node (ref "U7") (pin "4") (pinfunction "4_4") (pintype "passive"))
    )
    (net (code "78") (name "/VC-Motor2") (class "Default")
      (node (ref "H2") (pin "6") (pinfunction "11_6") (pintype "passive"))
      (node (ref "U8") (pin "1") (pinfunction "1_1") (pintype "passive"))
      (node (ref "U8") (pin "4") (pinfunction "4_4") (pintype "passive"))
    )
    (net (code "81") (name "/VDCA_Out") (class "Default")
      (node (ref "J1") (pin "45") (pinfunction "45_45") (pintype "passive"))
      (node (ref "R6") (pin "1") (pinfunction "1_1") (pintype "passive"))
      (node (ref "TP8") (pin "1") (pinfunction "1_1") (pintype "passive"))
      (node (ref "U2") (pin "7") (pinfunction "7_7") (pintype "passive"))
    )
    (net (code "82") (name "/VDCB_Out") (class "Default")
      (node (ref "J1") (pin "09") (pinfunction "09_09") (pintype "passive"))
      (node (ref "R26") (pin "1") (pinfunction "1_1") (pintype "passive"))
      (node (ref "U10") (pin "7") (pinfunction "7_7") (pintype "passive"))
    )
    (net (code "84") (name "/V_capA_1") (class "Default")
      (node (ref "J1") (pin "27") (pinfunction "27_27") (pintype "passive"))
      (node (ref "TP1") (pin "1") (pinfunction "1_1") (pintype "passive"))
    )
    (net (code "88") (name "/V_capB_1") (class "Default")
      (node (ref "J1") (pin "29") (pinfunction "29_29") (pintype "passive"))
      (node (ref "TP2") (pin "1") (pinfunction "1_1") (pintype "passive"))
    )
    (net (code "92") (name "/V_capC_1") (class "Default")
      (node (ref "J1") (pin "31") (pinfunction "31_31") (pintype "passive"))
      (node (ref "TP3") (pin "1") (pinfunction "1_1") (pintype "passive"))
    )
    (net (code "107") (name "3.3A") (class "Default")
      (node (ref "C1") (pin "2") (pinfunction "2_2") (pintype "passive"))
      (node (ref "R1") (pin "2") (pinfunction "2_2") (pintype "passive"))
    )
    (net (code "108") (name "3.3B") (class "Default")
      (node (ref "C11") (pin "2") (pinfunction "2_2") (pintype "passive"))
      (node (ref "J1") (pin "15") (pinfunction "15_15") (pintype "passive"))
      (node (ref "R19") (pin "2") (pinfunction "2_2") (pintype "passive"))
    )
    (net (code "109") (name "5V") (class "Default")
      (node (ref "H1") (pin "8") (pinfunction "12_8") (pintype "passive"))
      (node (ref "H2") (pin "8") (pinfunction "12_8") (pintype "passive"))
    )
    (net (code "110") (name "EPWM1A") (class "Default")
      (node (ref "J2") (pin "01") (pinfunction "01_01") (pintype "passive"))
    )
    (net (code "111") (name "EPWM1B") (class "Default")
      (node (ref "J2") (pin "03") (pinfunction "03_03") (pintype "passive"))
    )
    (net (code "112") (name "EPWM2A") (class "Default")
      (node (ref "J2") (pin "05") (pinfunction "05_05") (pintype "passive"))
    )
    (net (code "113") (name "EPWM2B") (class "Default")
      (node (ref "J2") (pin "07") (pinfunction "07_07") (pintype "passive"))
    )
    (net (code "114") (name "EPWM3A") (class "Default")
      (node (ref "J2") (pin "09") (pinfunction "09_09") (pintype "passive"))
    )
    (net (code "115") (name "EPWM3B") (class "Default")
      (node (ref "J2") (pin "11") (pinfunction "11_11") (pintype "passive"))
    )
    (net (code "116") (name "EPWM4A") (class "Default")
      (node (ref "J2") (pin "13") (pinfunction "13_13") (pintype "passive"))
    )
    (net (code "117") (name "EPWM4B") (class "Default")
      (node (ref "J2") (pin "15") (pinfunction "15_15") (pintype "passive"))
    )
    (net (code "118") (name "EPWM5A") (class "Default")
      (node (ref "J2") (pin "17") (pinfunction "17_17") (pintype "passive"))
    )
    (net (code "119") (name "EPWM5B") (class "Default")
      (node (ref "J2") (pin "19") (pinfunction "19_19") (pintype "passive"))
    )
    (net (code "120") (name "EPWM6A") (class "Default")
      (node (ref "J2") (pin "21") (pinfunction "21_21") (pintype "passive"))
    )
    (net (code "121") (name "EPWM6B") (class "Default")
      (node (ref "J2") (pin "23") (pinfunction "23_23") (pintype "passive"))
    )
    (net (code "122") (name "GND") (class "Default")
      (node (ref "C10") (pin "1") (pinfunction "1_1") (pintype "passive"))
      (node (ref "C12") (pin "1") (pinfunction "1_1") (pintype "passive"))
      (node (ref "C13") (pin "1") (pinfunction "1_1") (pintype "passive"))
      (node (ref "C14") (pin "1") (pinfunction "1_1") (pintype "passive"))
      (node (ref "C15") (pin "1") (pinfunction "1_1") (pintype "passive"))
      (node (ref "C16") (pin "1") (pinfunction "1_1") (pintype "passive"))
      (node (ref "C17") (pin "1") (pinfunction "1_1") (pintype "passive"))
      (node (ref "C18") (pin "1") (pinfunction "1_1") (pintype "passive"))
      (node (ref "C19") (pin "1") (pinfunction "1_1") (pintype "passive"))
      (node (ref "C2") (pin "1") (pinfunction "1_1") (pintype "passive"))
      (node (ref "C20") (pin "1") (pinfunction "1_1") (pintype "passive"))
      (node (ref "C21") (pin "1") (pinfunction "1_1") (pintype "passive"))
      (node (ref "C22") (pin "1") (pinfunction "1_1") (pintype "passive"))
      (node (ref "C22") (pin "2") (pinfunction "2_2") (pintype "passive"))
      (node (ref "C23") (pin "1") (pinfunction "1_1") (pintype "passive"))
      (node (ref "C23") (pin "2") (pinfunction "2_2") (pintype "passive"))
      (node (ref "C3") (pin "1") (pinfunction "1_1") (pintype "passive"))
      (node (ref "C4") (pin "1") (pinfunction "1_1") (pintype "passive"))
      (node (ref "C5") (pin "1") (pinfunction "1_1") (pintype "passive"))
      (node (ref "C6") (pin "1") (pinfunction "1_1") (pintype "passive"))
      (node (ref "C7") (pin "1") (pinfunction "1_1") (pintype "passive"))
      (node (ref "C8") (pin "1") (pinfunction "1_1") (pintype "passive"))
      (node (ref "C9") (pin "1") (pinfunction "1_1") (pintype "passive"))
      (node (ref "H1") (pin "13") (pinfunction "7_13") (pintype "passive"))
      (node (ref "H2") (pin "13") (pinfunction "7_13") (pintype "passive"))
      (node (ref "J1") (pin "01") (pinfunction "01_01") (pintype "passive"))
      (node (ref "J1") (pin "02") (pinfunction "02_02") (pintype "passive"))
      (node (ref "J1") (pin "03") (pinfunction "03_03") (pintype "passive"))
      (node (ref "J1") (pin "04") (pinfunction "04_04") (pintype "passive"))
      (node (ref "J1") (pin "05") (pinfunction "05_05") (pintype "passive"))
      (node (ref "J1") (pin "06") (pinfunction "06_06") (pintype "passive"))
      (node (ref "J1") (pin "07") (pinfunction "07_07") (pintype "passive"))
      (node (ref "J1") (pin "08") (pinfunction "08_08") (pintype "passive"))
      (node (ref "J1") (pin "10") (pinfunction "10_10") (pintype "passive"))
      (node (ref "J1") (pin "13") (pinfunction "13_13") (pintype "passive"))
      (node (ref "J1") (pin "14") (pinfunction "14_14") (pintype "passive"))
      (node (ref "J1") (pin "16") (pinfunction "16_16") (pintype "passive"))
      (node (ref "J1") (pin "17") (pinfunction "17_17") (pintype "passive"))
      (node (ref "J1") (pin "18") (pinfunction "18_18") (pintype "passive"))
      (node (ref "J1") (pin "19") (pinfunction "19_19") (pintype "passive"))
      (node (ref "J1") (pin "20") (pinfunction "20_20") (pintype "passive"))
      (node (ref "J1") (pin "21") (pinfunction "21_21") (pintype "passive"))
      (node (ref "J1") (pin "22") (pinfunction "22_22") (pintype "passive"))
      (node (ref "J1") (pin "25") (pinfunction "25_25") (pintype "passive"))
      (node (ref "J1") (pin "26") (pinfunction "26_26") (pintype "passive"))
      (node (ref "J1") (pin "28") (pinfunction "28_28") (pintype "passive"))
      (node (ref "J1") (pin "30") (pinfunction "30_30") (pintype "passive"))
      (node (ref "J1") (pin "32") (pinfunction "32_32") (pintype "passive"))
      (node (ref "J1") (pin "34") (pinfunction "34_34") (pintype "passive"))
      (node (ref "J1") (pin "37") (pinfunction "37_37") (pintype "passive"))
      (node (ref "J1") (pin "38") (pinfunction "38_38") (pintype "passive"))
      (node (ref "J1") (pin "40") (pinfunction "40_40") (pintype "passive"))
      (node (ref "J1") (pin "42") (pinfunction "42_42") (pintype "passive"))
      (node (ref "J1") (pin "44") (pinfunction "44_44") (pintype "passive"))
      (node (ref "J1") (pin "46") (pinfunction "46_46") (pintype "passive"))
      (node (ref "J1") (pin "49") (pinfunction "49_49") (pintype "passive"))
      (node (ref "J1") (pin "50") (pinfunction "50_50") (pintype "passive"))
      (node (ref "J2") (pin "02") (pinfunction "02_02") (pintype "passive"))
      (node (ref "J2") (pin "04") (pinfunction "04_04") (pintype "passive"))
      (node (ref "J2") (pin "06") (pinfunction "06_06") (pintype "passive"))
      (node (ref "J2") (pin "08") (pinfunction "08_08") (pintype "passive"))
      (node (ref "J2") (pin "10") (pinfunction "10_10") (pintype "passive"))
      (node (ref "J2") (pin "12") (pinfunction "12_12") (pintype "passive"))
      (node (ref "J2") (pin "14") (pinfunction "14_14") (pintype "passive"))
      (node (ref "J2") (pin "16") (pinfunction "16_16") (pintype "passive"))
      (node (ref "J2") (pin "18") (pinfunction "18_18") (pintype "passive"))
      (node (ref "J2") (pin "20") (pinfunction "20_20") (pintype "passive"))
      (node (ref "J2") (pin "22") (pinfunction "22_22") (pintype "passive"))
      (node (ref "J2") (pin "24") (pinfunction "24_24") (pintype "passive"))
      (node (ref "J2") (pin "26") (pinfunction "26_26") (pintype "passive"))
      (node (ref "J2") (pin "28") (pinfunction "28_28") (pintype "passive"))
      (node (ref "J2") (pin "30") (pinfunction "30_30") (pintype "passive"))
      (node (ref "J2") (pin "32") (pinfunction "32_32") (pintype "passive"))
      (node (ref "J2") (pin "34") (pinfunction "34_34") (pintype "passive"))
      (node (ref "J2") (pin "36") (pinfunction "36_36") (pintype "passive"))
      (node (ref "J2") (pin "38") (pinfunction "38_38") (pintype "passive"))
      (node (ref "J2") (pin "40") (pinfunction "40_40") (pintype "passive"))
      (node (ref "PE1") (pin "1") (pinfunction "PE_1") (pintype "passive"))
      (node (ref "PE2") (pin "1") (pinfunction "PE_1") (pintype "passive"))
      (node (ref "R14") (pin "2") (pinfunction "2_2") (pintype "passive"))
      (node (ref "R16") (pin "1") (pinfunction "1_1") (pintype "passive"))
      (node (ref "R18") (pin "1") (pinfunction "1_1") (pintype "passive"))
      (node (ref "R2") (pin "1") (pinfunction "1_1") (pintype "passive"))
      (node (ref "R20") (pin "1") (pinfunction "1_1") (pintype "passive"))
      (node (ref "R29") (pin "1") (pinfunction "1_1") (pintype "passive"))
      (node (ref "R36") (pin "2") (pinfunction "2_2") (pintype "passive"))
      (node (ref "R38") (pin "1") (pinfunction "1_1") (pintype "passive"))
      (node (ref "R40") (pin "1") (pinfunction "1_1") (pintype "passive"))
      (node (ref "R9") (pin "1") (pinfunction "1_1") (pintype "passive"))
      (node (ref "TP10") (pin "1") (pinfunction "1_1") (pintype "passive"))
    )
    (net (code "131") (name "I_InA_1") (class "Default")
      (node (ref "R4") (pin "2") (pinfunction "2_2") (pintype "passive"))
    )
    (net (code "132") (name "I_InA_2") (class "Default")
      (node (ref "R12") (pin "2") (pinfunction "2_2") (pintype "passive"))
    )
    (net (code "133") (name "I_InA_3") (class "Default")
      (node (ref "R17") (pin "2") (pinfunction "2_2") (pintype "passive"))
    )
    (net (code "134") (name "I_InB_1") (class "Default")
      (node (ref "R22") (pin "2") (pinfunction "2_2") (pintype "passive"))
    )
    (net (code "135") (name "I_InB_2") (class "Default")
      (node (ref "R34") (pin "2") (pinfunction "2_2") (pintype "passive"))
    )
    (net (code "136") (name "I_InB_3") (class "Default")
      (node (ref "R39") (pin "2") (pinfunction "2_2") (pintype "passive"))
    )
    (net (code "137") (name "Net-(C1-Pad1)") (class "Default")
      (node (ref "C1") (pin "1") (pinfunction "1_1") (pintype "passive"))
      (node (ref "C2") (pin "2") (pinfunction "2_2") (pintype "passive"))
      (node (ref "R1") (pin "1") (pinfunction "1_1") (pintype "passive"))
      (node (ref "R2") (pin "2") (pinfunction "2_2") (pintype "passive"))
      (node (ref "U1") (pin "3") (pinfunction "3_3") (pintype "passive"))
      (node (ref "U2") (pin "3") (pinfunction "3_3") (pintype "passive"))
    )
    (net (code "138") (name "Net-(C11-Pad1)") (class "Default")
      (node (ref "C11") (pin "1") (pinfunction "1_1") (pintype "passive"))
      (node (ref "C12") (pin "2") (pinfunction "2_2") (pintype "passive"))
      (node (ref "R19") (pin "1") (pinfunction "1_1") (pintype "passive"))
      (node (ref "R20") (pin "2") (pinfunction "2_2") (pintype "passive"))
      (node (ref "U10") (pin "3") (pinfunction "3_3") (pintype "passive"))
      (node (ref "U9") (pin "3") (pinfunction "3_3") (pintype "passive"))
    )
    (net (code "139") (name "Net-(H1-6)") (class "Default")
      (node (ref "H1") (pin "11") (pinfunction "6_11") (pintype "passive"))
      (node (ref "R31") (pin "2") (pinfunction "2_2") (pintype "passive"))
    )
    (net (code "140") (name "Net-(H1-8)") (class "Default")
      (node (ref "H1") (pin "15") (pinfunction "8_15") (pintype "passive"))
      (node (ref "R24") (pin "1") (pinfunction "1_1") (pintype "passive"))
    )
    (net (code "141") (name "Net-(H1-14)") (class "Default")
      (node (ref "H1") (pin "12") (pinfunction "14_12") (pintype "passive"))
      (node (ref "R31") (pin "1") (pinfunction "1_1") (pintype "passive"))
    )
    (net (code "142") (name "Net-(H1-Pad1)") (class "Default")
      (node (ref "H1") (pin "1") (pinfunction "1_1") (pintype "passive"))
      (node (ref "R24") (pin "2") (pinfunction "2_2") (pintype "passive"))
    )
    (net (code "143") (name "Net-(H2-6)") (class "Default")
      (node (ref "H2") (pin "11") (pinfunction "6_11") (pintype "passive"))
      (node (ref "R32") (pin "2") (pinfunction "2_2") (pintype "passive"))
    )
    (net (code "144") (name "Net-(H2-8)") (class "Default")
      (node (ref "H2") (pin "15") (pinfunction "8_15") (pintype "passive"))
      (node (ref "R25") (pin "1") (pinfunction "1_1") (pintype "passive"))
    )
    (net (code "145") (name "Net-(H2-14)") (class "Default")
      (node (ref "H2") (pin "12") (pinfunction "14_12") (pintype "passive"))
      (node (ref "R32") (pin "1") (pinfunction "1_1") (pintype "passive"))
    )
    (net (code "146") (name "Net-(H2-Pad1)") (class "Default")
      (node (ref "H2") (pin "1") (pinfunction "1_1") (pintype "passive"))
      (node (ref "R25") (pin "2") (pinfunction "2_2") (pintype "passive"))
    )
    (net (code "147") (name "Net-(R3-Pad2)") (class "Default")
      (node (ref "R3") (pin "2") (pinfunction "2_2") (pintype "passive"))
      (node (ref "R5") (pin "1") (pinfunction "1_1") (pintype "passive"))
      (node (ref "U1") (pin "6") (pinfunction "6_6") (pintype "passive"))
    )
    (net (code "148") (name "Net-(R4-Pad1)") (class "Default")
      (node (ref "R4") (pin "1") (pinfunction "1_1") (pintype "passive"))
      (node (ref "R9") (pin "2") (pinfunction "2_2") (pintype "passive"))
      (node (ref "U1") (pin "5") (pinfunction "5_5") (pintype "passive"))
    )
    (net (code "149") (name "Net-(R6-Pad2)") (class "Default")
      (node (ref "R6") (pin "2") (pinfunction "2_2") (pintype "passive"))
      (node (ref "R7") (pin "2") (pinfunction "2_2") (pintype "passive"))
      (node (ref "U2") (pin "6") (pinfunction "6_6") (pintype "passive"))
    )
    (net (code "150") (name "Net-(R10-Pad1)") (class "Default")
      (node (ref "R10") (pin "1") (pinfunction "1_1") (pintype "passive"))
      (node (ref "R8") (pin "2") (pinfunction "2_2") (pintype "passive"))
      (node (ref "U1") (pin "9") (pinfunction "9_9") (pintype "passive"))
    )
    (net (code "151") (name "Net-(R11-Pad2)") (class "Default")
      (node (ref "R11") (pin "2") (pinfunction "2_2") (pintype "passive"))
      (node (ref "R14") (pin "1") (pinfunction "1_1") (pintype "passive"))
      (node (ref "U2") (pin "5") (pinfunction "5_5") (pintype "passive"))
    )
    (net (code "152") (name "Net-(R12-Pad1)") (class "Default")
      (node (ref "R12") (pin "1") (pinfunction "1_1") (pintype "passive"))
      (node (ref "R16") (pin "2") (pinfunction "2_2") (pintype "passive"))
      (node (ref "U1") (pin "10") (pinfunction "10_10") (pintype "passive"))
    )
    (net (code "153") (name "Net-(R13-Pad2)") (class "Default")
      (node (ref "R13") (pin "2") (pinfunction "2_2") (pintype "passive"))
      (node (ref "R15") (pin "1") (pinfunction "1_1") (pintype "passive"))
      (node (ref "U1") (pin "13") (pinfunction "13_13") (pintype "passive"))
    )
    (net (code "154") (name "Net-(R17-Pad1)") (class "Default")
      (node (ref "R17") (pin "1") (pinfunction "1_1") (pintype "passive"))
      (node (ref "R18") (pin "2") (pinfunction "2_2") (pintype "passive"))
      (node (ref "U1") (pin "12") (pinfunction "12_12") (pintype "passive"))
    )
    (net (code "155") (name "Net-(R21-Pad2)") (class "Default")
      (node (ref "R21") (pin "2") (pinfunction "2_2") (pintype "passive"))
      (node (ref "R23") (pin "1") (pinfunction "1_1") (pintype "passive"))
      (node (ref "U9") (pin "6") (pinfunction "6_6") (pintype "passive"))
    )
    (net (code "156") (name "Net-(R22-Pad1)") (class "Default")
      (node (ref "R22") (pin "1") (pinfunction "1_1") (pintype "passive"))
      (node (ref "R29") (pin "2") (pinfunction "2_2") (pintype "passive"))
      (node (ref "U9") (pin "5") (pinfunction "5_5") (pintype "passive"))
    )
    (net (code "157") (name "Net-(R26-Pad2)") (class "Default")
      (node (ref "R26") (pin "2") (pinfunction "2_2") (pintype "passive"))
      (node (ref "R27") (pin "2") (pinfunction "2_2") (pintype "passive"))
      (node (ref "U10") (pin "6") (pinfunction "6_6") (pintype "passive"))
    )
    (net (code "158") (name "Net-(R28-Pad2)") (class "Default")
      (node (ref "R28") (pin "2") (pinfunction "2_2") (pintype "passive"))
      (node (ref "R30") (pin "1") (pinfunction "1_1") (pintype "passive"))
      (node (ref "U9") (pin "9") (pinfunction "9_9") (pintype "passive"))
    )
    (net (code "159") (name "Net-(R33-Pad2)") (class "Default")
      (node (ref "R33") (pin "2") (pinfunction "2_2") (pintype "passive"))
      (node (ref "R36") (pin "1") (pinfunction "1_1") (pintype "passive"))
      (node (ref "U10") (pin "5") (pinfunction "5_5") (pintype "passive"))
    )
    (net (code "160") (name "Net-(R34-Pad1)") (class "Default")
      (node (ref "R34") (pin "1") (pinfunction "1_1") (pintype "passive"))
      (node (ref "R38") (pin "2") (pinfunction "2_2") (pintype "passive"))
      (node (ref "U9") (pin "10") (pinfunction "10_10") (pintype "passive"))
    )
    (net (code "161") (name "Net-(R35-Pad2)") (class "Default")
      (node (ref "R35") (pin "2") (pinfunction "2_2") (pintype "passive"))
      (node (ref "R37") (pin "1") (pinfunction "1_1") (pintype "passive"))
      (node (ref "U9") (pin "13") (pinfunction "13_13") (pintype "passive"))
    )
    (net (code "162") (name "Net-(R39-Pad1)") (class "Default")
      (node (ref "R39") (pin "1") (pinfunction "1_1") (pintype "passive"))
      (node (ref "R40") (pin "2") (pinfunction "2_2") (pintype "passive"))
      (node (ref "U9") (pin "12") (pinfunction "12_12") (pintype "passive"))
    )
    (net (code "175") (name "PWM_EN_1") (class "Default")
      (node (ref "J2") (pin "35") (pinfunction "35_35") (pintype "passive"))
      (node (ref "TP4") (pin "1") (pinfunction "1_1") (pintype "passive"))
    )
    (net (code "176") (name "PWM_EN_2") (class "Default")
      (node (ref "J2") (pin "47") (pinfunction "47_47") (pintype "passive"))
      (node (ref "TP9") (pin "1") (pinfunction "1_1") (pintype "passive"))
    )
    (net (code "177") (name "VDCA_In") (class "Default")
      (node (ref "R11") (pin "1") (pinfunction "1_1") (pintype "passive"))
    )
    (net (code "178") (name "VDCB_In") (class "Default")
      (node (ref "R33") (pin "1") (pinfunction "1_1") (pintype "passive"))
    )
    (net (code "179") (name "VREFA") (class "Default")
      (node (ref "J1") (pin "33") (pinfunction "33_33") (pintype "passive"))
    )
    (net (code "180") (name "unconnected-(H1-2-Pad3)") (class "Default")
      (node (ref "H1") (pin "3") (pinfunction "2_3") (pintype "passive+no_connect"))
    )
    (net (code "181") (name "unconnected-(H1-3-Pad5)") (class "Default")
      (node (ref "H1") (pin "5") (pinfunction "3_5") (pintype "passive+no_connect"))
    )
    (net (code "182") (name "unconnected-(H1-4-Pad7)") (class "Default")
      (node (ref "H1") (pin "7") (pinfunction "4_7") (pintype "passive+no_connect"))
    )
    (net (code "183") (name "unconnected-(H1-5-Pad9)") (class "Default")
      (node (ref "H1") (pin "9") (pinfunction "5_9") (pintype "passive+no_connect"))
    )
    (net (code "184") (name "unconnected-(H2-2-Pad3)") (class "Default")
      (node (ref "H2") (pin "3") (pinfunction "2_3") (pintype "passive+no_connect"))
    )
    (net (code "185") (name "unconnected-(H2-3-Pad5)") (class "Default")
      (node (ref "H2") (pin "5") (pinfunction "3_5") (pintype "passive+no_connect"))
    )
    (net (code "186") (name "unconnected-(H2-4-Pad7)") (class "Default")
      (node (ref "H2") (pin "7") (pinfunction "4_7") (pintype "passive+no_connect"))
    )
    (net (code "187") (name "unconnected-(H2-5-Pad9)") (class "Default")
      (node (ref "H2") (pin "9") (pinfunction "5_9") (pintype "passive+no_connect"))
    )
    (net (code "188") (name "unconnected-(J2-Pad25)") (class "Default")
      (node (ref "J2") (pin "25") (pinfunction "25_25") (pintype "passive"))
    )
    (net (code "189") (name "unconnected-(J2-Pad27)") (class "Default")
      (node (ref "J2") (pin "27") (pinfunction "27_27") (pintype "passive"))
    )
    (net (code "190") (name "unconnected-(J2-Pad29)") (class "Default")
      (node (ref "J2") (pin "29") (pinfunction "29_29") (pintype "passive"))
    )
    (net (code "191") (name "unconnected-(J2-Pad31)") (class "Default")
      (node (ref "J2") (pin "31") (pinfunction "31_31") (pintype "passive"))
    )
    (net (code "192") (name "unconnected-(J2-Pad33)") (class "Default")
      (node (ref "J2") (pin "33") (pinfunction "33_33") (pintype "passive"))
    )
    (net (code "193") (name "unconnected-(J2-Pad37)") (class "Default")
      (node (ref "J2") (pin "37") (pinfunction "37_37") (pintype "passive"))
    )
    (net (code "194") (name "unconnected-(J2-Pad39)") (class "Default")
      (node (ref "J2") (pin "39") (pinfunction "39_39") (pintype "passive"))
    )
    (net (code "195") (name "unconnected-(J2-Pad41)") (class "Default")
      (node (ref "J2") (pin "41") (pinfunction "41_41") (pintype "passive"))
    )
    (net (code "196") (name "unconnected-(J2-Pad42)") (class "Default")
      (node (ref "J2") (pin "42") (pinfunction "42_42") (pintype "passive"))
    )
    (net (code "197") (name "unconnected-(J2-Pad43)") (class "Default")
      (node (ref "J2") (pin "43") (pinfunction "43_43") (pintype "passive"))
    )
    (net (code "198") (name "unconnected-(J2-Pad44)") (class "Default")
      (node (ref "J2") (pin "44") (pinfunction "44_44") (pintype "passive"))
    )
    (net (code "199") (name "unconnected-(J2-Pad45)") (class "Default")
      (node (ref "J2") (pin "45") (pinfunction "45_45") (pintype "passive"))
    )
    (net (code "200") (name "unconnected-(J2-Pad46)") (class "Default")
      (node (ref "J2") (pin "46") (pinfunction "46_46") (pintype "passive"))
    )
    (net (code "201") (name "unconnected-(J2-Pad48)") (class "Default")
      (node (ref "J2") (pin "48") (pinfunction "48_48") (pintype "passive"))
    )
    (net (code "202") (name "unconnected-(J2-Pad49)") (class "Default")
      (node (ref "J2") (pin "49") (pinfunction "49_49") (pintype "passive"))
    )
    (net (code "203") (name "unconnected-(J2-Pad50)") (class "Default")
      (node (ref "J2") (pin "50") (pinfunction "50_50") (pintype "passive"))
    )
    (net (code "204") (name "unconnected-(J4-Pad1)") (class "Default")
      (node (ref "J4") (pin "1") (pinfunction "1_1") (pintype "passive"))
    )
    (net (code "205") (name "unconnected-(J5-Pad1)") (class "Default")
      (node (ref "J5") (pin "1") (pinfunction "1_1") (pintype "passive"))
    )
    (net (code "206") (name "unconnected-(J6-Pad1)") (class "Default")
      (node (ref "J6") (pin "1") (pinfunction "1_1") (pintype "passive"))
    )
    (net (code "207") (name "unconnected-(J7-Pad1)") (class "Default")
      (node (ref "J7") (pin "1") (pinfunction "1_1") (pintype "passive"))
    )
    (net (code "208") (name "unconnected-(J8-Pad1)") (class "Default")
      (node (ref "J8") (pin "1") (pinfunction "1_1") (pintype "passive"))
    )
    (net (code "209") (name "unconnected-(J9-Pad1)") (class "Default")
      (node (ref "J9") (pin "1") (pinfunction "1_1") (pintype "passive"))
    )
    (net (code "210") (name "unconnected-(J10-Pad1)") (class "Default")
      (node (ref "J10") (pin "1") (pinfunction "1_1") (pintype "passive"))
    )
    (net (code "211") (name "unconnected-(J11-Pad1)") (class "Default")
      (node (ref "J11") (pin "1") (pinfunction "1_1") (pintype "passive"))
    )
    (net (code "212") (name "unconnected-(J12-Pad1)") (class "Default")
      (node (ref "J12") (pin "1") (pinfunction "1_1") (pintype "passive"))
    )
    (net (code "213") (name "unconnected-(U2-Pad8)") (class "Default")
      (node (ref "U2") (pin "8") (pinfunction "8_8") (pintype "passive"))
    )
    (net (code "214") (name "unconnected-(U2-Pad9)") (class "Default")
      (node (ref "U2") (pin "9") (pinfunction "9_9") (pintype "passive"))
    )
    (net (code "215") (name "unconnected-(U2-Pad10)") (class "Default")
      (node (ref "U2") (pin "10") (pinfunction "10_10") (pintype "passive"))
    )
    (net (code "216") (name "unconnected-(U2-Pad12)") (class "Default")
      (node (ref "U2") (pin "12") (pinfunction "12_12") (pintype "passive"))
    )
    (net (code "217") (name "unconnected-(U2-Pad13)") (class "Default")
      (node (ref "U2") (pin "13") (pinfunction "13_13") (pintype "passive"))
    )
    (net (code "218") (name "unconnected-(U2-Pad14)") (class "Default")
      (node (ref "U2") (pin "14") (pinfunction "14_14") (pintype "passive"))
    )
    (net (code "219") (name "unconnected-(U3-Pad2)") (class "Default")
      (node (ref "U3") (pin "2") (pinfunction "2_2") (pintype "passive"))
    )
    (net (code "220") (name "unconnected-(U3-Pad3)") (class "Default")
      (node (ref "U3") (pin "3") (pinfunction "3_3") (pintype "passive"))
    )
    (net (code "221") (name "unconnected-(U4-Pad2)") (class "Default")
      (node (ref "U4") (pin "2") (pinfunction "2_2") (pintype "passive"))
    )
    (net (code "222") (name "unconnected-(U4-Pad3)") (class "Default")
      (node (ref "U4") (pin "3") (pinfunction "3_3") (pintype "passive"))
    )
    (net (code "223") (name "unconnected-(U5-Pad2)") (class "Default")
      (node (ref "U5") (pin "2") (pinfunction "2_2") (pintype "passive"))
    )
    (net (code "224") (name "unconnected-(U5-Pad3)") (class "Default")
      (node (ref "U5") (pin "3") (pinfunction "3_3") (pintype "passive"))
    )
    (net (code "225") (name "unconnected-(U6-Pad2)") (class "Default")
      (node (ref "U6") (pin "2") (pinfunction "2_2") (pintype "passive"))
    )
    (net (code "226") (name "unconnected-(U6-Pad3)") (class "Default")
      (node (ref "U6") (pin "3") (pinfunction "3_3") (pintype "passive"))
    )
    (net (code "227") (name "unconnected-(U7-Pad2)") (class "Default")
      (node (ref "U7") (pin "2") (pinfunction "2_2") (pintype "passive"))
    )
    (net (code "228") (name "unconnected-(U7-Pad3)") (class "Default")
      (node (ref "U7") (pin "3") (pinfunction "3_3") (pintype "passive"))
    )
    (net (code "229") (name "unconnected-(U8-Pad2)") (class "Default")
      (node (ref "U8") (pin "2") (pinfunction "2_2") (pintype "passive"))
    )
    (net (code "230") (name "unconnected-(U8-Pad3)") (class "Default")
      (node (ref "U8") (pin "3") (pinfunction "3_3") (pintype "passive"))
    )
    (net (code "231") (name "unconnected-(U10-Pad8)") (class "Default")
      (node (ref "U10") (pin "8") (pinfunction "8_8") (pintype "passive"))
    )
    (net (code "232") (name "unconnected-(U10-Pad9)") (class "Default")
      (node (ref "U10") (pin "9") (pinfunction "9_9") (pintype "passive"))
    )
    (net (code "233") (name "unconnected-(U10-Pad10)") (class "Default")
      (node (ref "U10") (pin "10") (pinfunction "10_10") (pintype "passive"))
    )
    (net (code "234") (name "unconnected-(U10-Pad12)") (class "Default")
      (node (ref "U10") (pin "12") (pinfunction "12_12") (pintype "passive"))
    )
    (net (code "235") (name "unconnected-(U10-Pad13)") (class "Default")
      (node (ref "U10") (pin "13") (pinfunction "13_13") (pintype "passive"))
    )
    (net (code "236") (name "unconnected-(U10-Pad14)") (class "Default")
      (node (ref "U10") (pin "14") (pinfunction "14_14") (pintype "passive"))
    )
  )
)
